# VS_Project_HW02.net
KiCad netlist of a schematic drawn in EasyEDA Pro
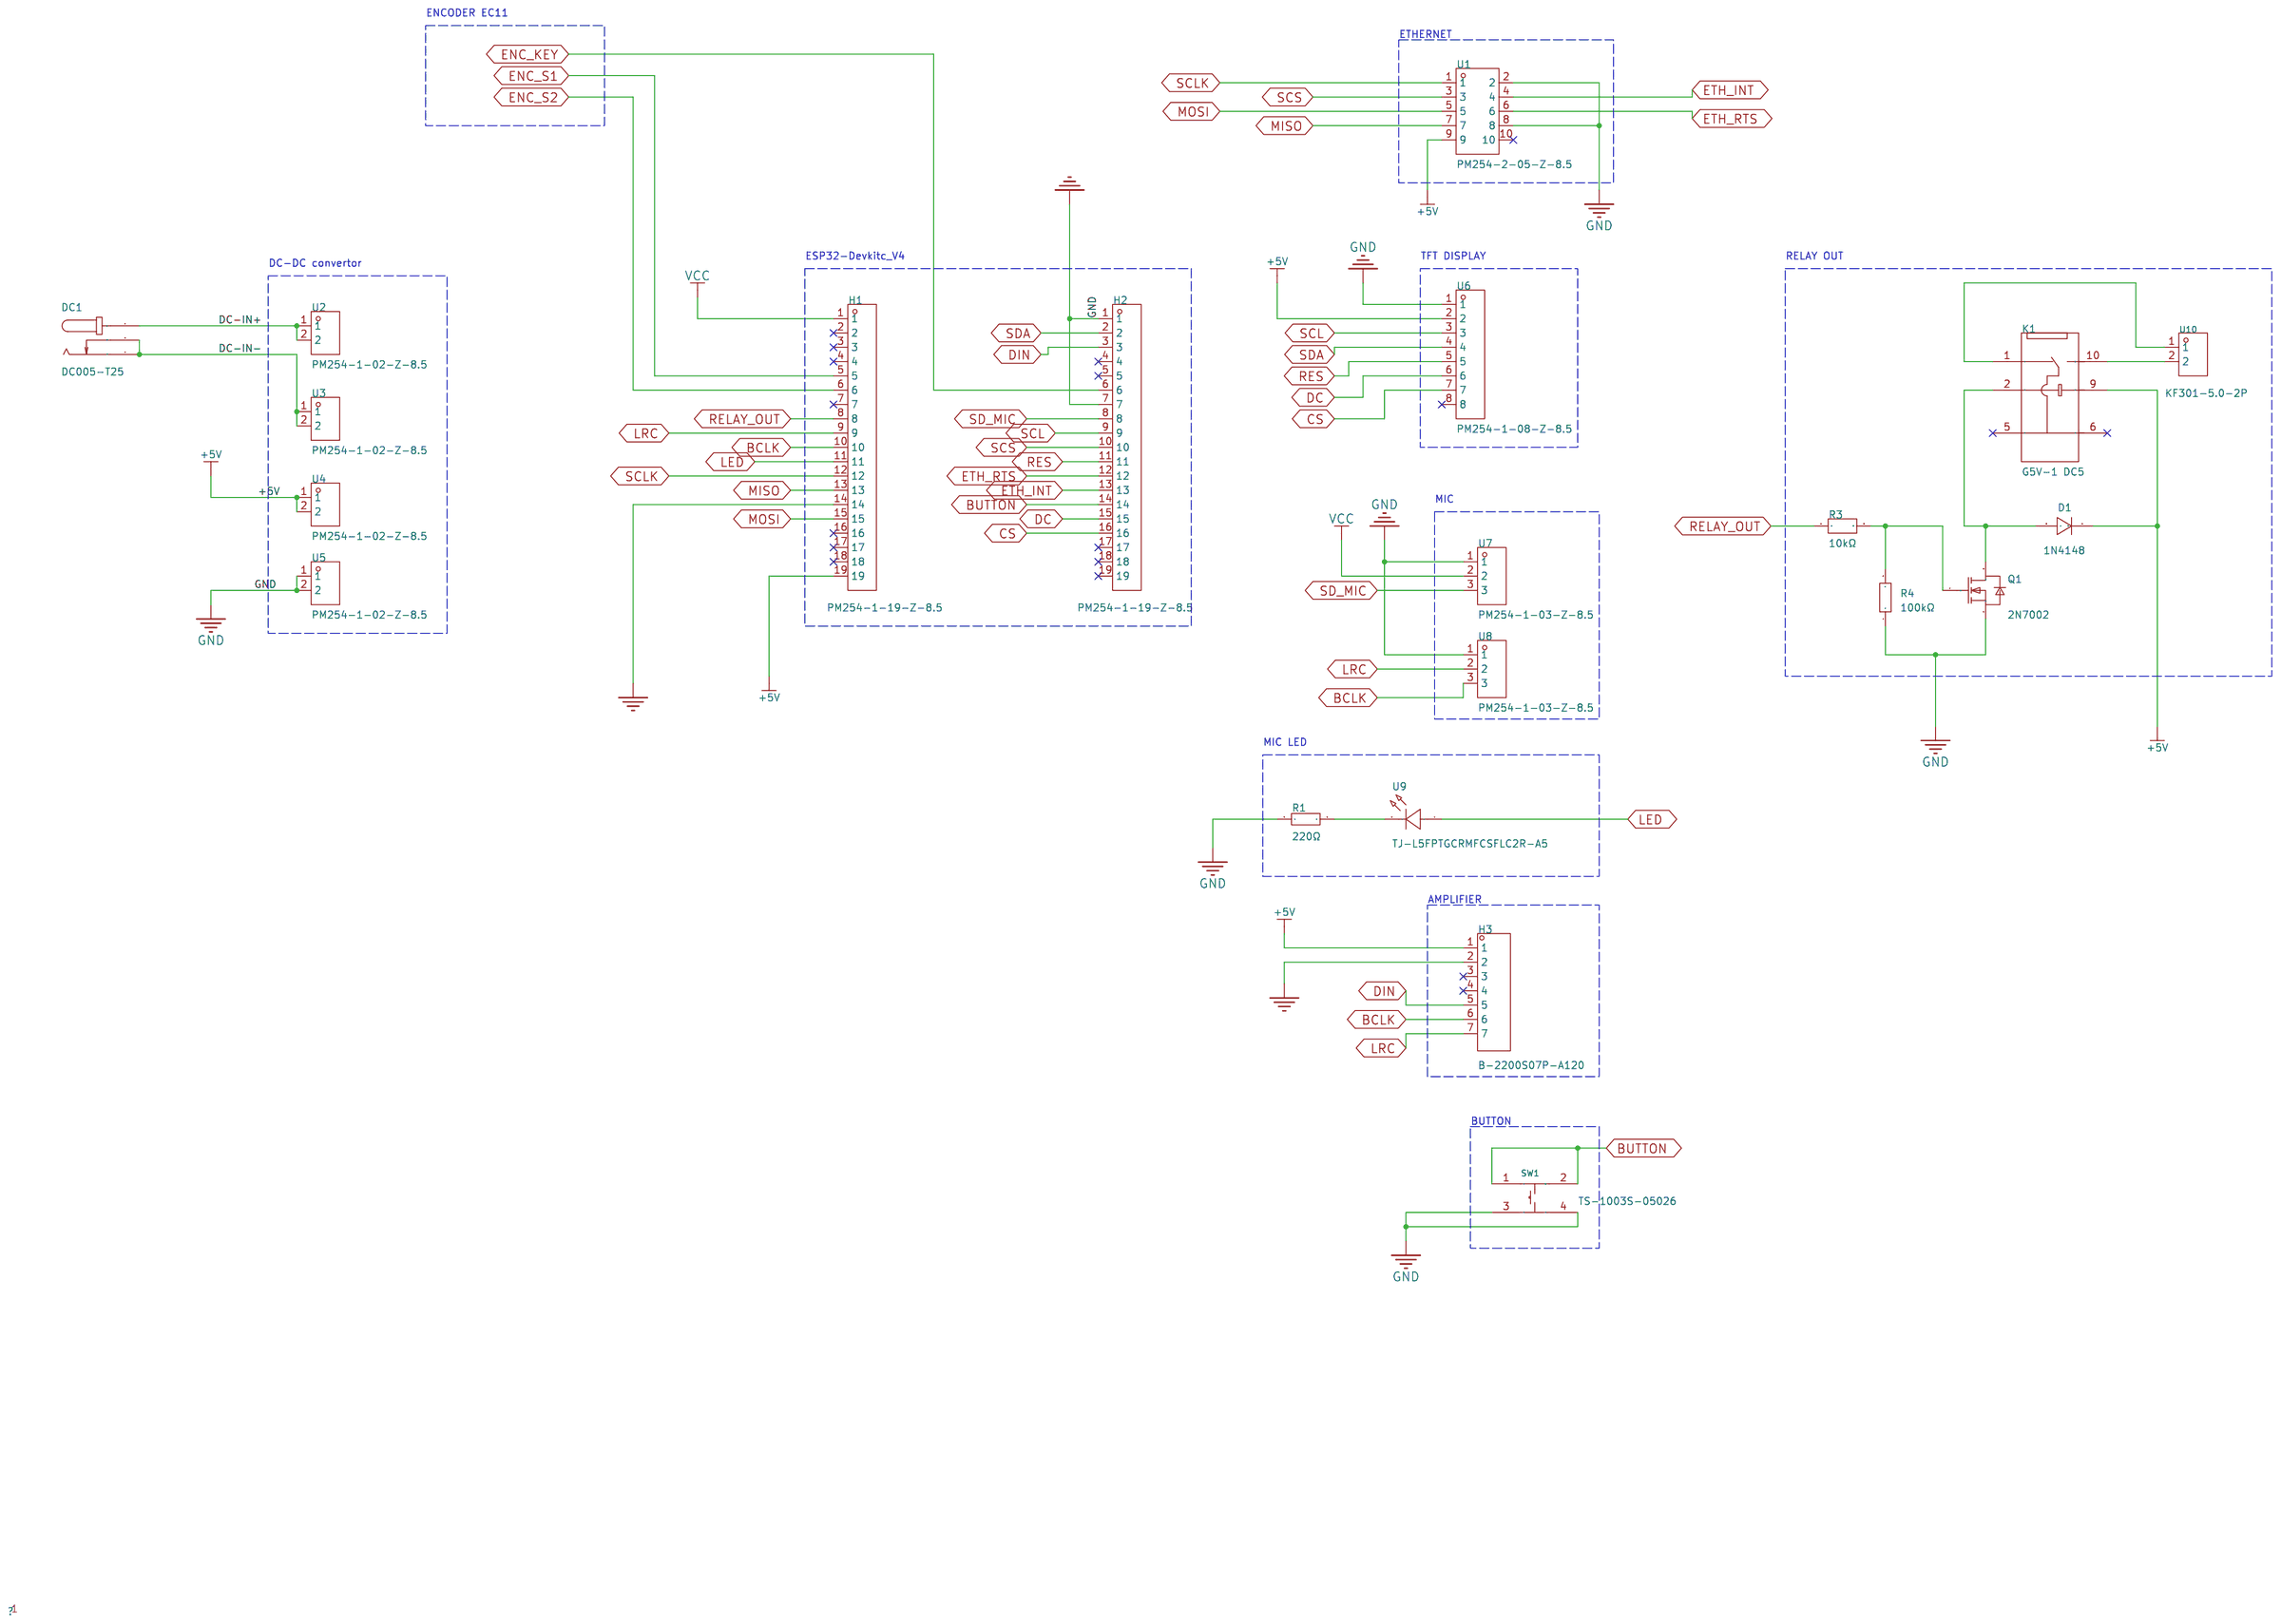
[diagram p0: schematic sheet]

(export (version "E")
  (design (tool "Eeschema 10.0.6"))
  (components
    (comp (ref "D1")
      (value "1N4148")
      (footprint "easyedapro:DO-35_BD2.0-L4.2-P8.20-D0.5-RD")
      (fields (field (name "Manufacturer") "GOOD-ARK(固锝)"))
      (libsource (lib "easyedapro") (part "1N4148_C406389"))
    )
    (comp (ref "DC1")
      (value "DC005-T25")
      (footprint "easyedapro:DC-IN-TH_DC-005-20A-1")
      (fields (field (name "Manufacturer") "SOFNG(硕方)"))
      (libsource (lib "easyedapro") (part "DC005-2.5MM"))
    )
    (comp (ref "H1")
      (value "PM254-1-19-Z-8.5")
      (footprint "easyedapro:HDR-TH_19P-P2.54-V-F")
      (fields (field (name "Manufacturer") "HCTL(华灿天禄)"))
      (libsource (lib "easyedapro") (part "HDR-F_2.54_1x19P"))
    )
    (comp (ref "H2")
      (value "PM254-1-19-Z-8.5")
      (footprint "easyedapro:HDR-TH_19P-P2.54-V-F")
      (fields (field (name "Manufacturer") "HCTL(华灿天禄)"))
      (libsource (lib "easyedapro") (part "HDR-F_2.54_1x19P"))
    )
    (comp (ref "H3")
      (value "B-2200S07P-A120")
      (footprint "easyedapro:HDR-TH_7P-P2.54-V-F")
      (fields (field (name "Manufacturer") "Ckmtw(灿科盟)"))
      (libsource (lib "easyedapro") (part "220S-1*7P H=8.5MM Ytype Gold-plated"))
    )
    (comp (ref "K1")
      (value "G5V-1 DC5")
      (footprint "easyedapro:RELAY-TH_G5V-1")
      (fields (field (name "Manufacturer") "OMRON(欧姆龙)"))
      (libsource (lib "easyedapro") (part "G5V-1-DC3"))
    )
    (comp (ref "Q1")
      (value "2N7002")
      (footprint "easyedapro:SOT-23-3_L2.9-W1.3-P1.90-LS2.4-BR")
      (fields (field (name "Manufacturer") "YFW(佑风微)"))
      (libsource (lib "easyedapro") (part "2N7002_C42395051"))
    )
    (comp (ref "R1")
      (value "220Ω")
      (footprint "easyedapro:R0603")
      (fields (field (name "Manufacturer Part") "RC0603FR-07220RL") (field (name "Manufacturer") "YAGEO(国巨)"))
      (libsource (lib "easyedapro") (part "Res"))
    )
    (comp (ref "R3")
      (value "10kΩ")
      (footprint "easyedapro:R0603")
      (fields (field (name "Manufacturer Part") "RC0603JR-0710KL") (field (name "Manufacturer") "YAGEO(国巨)"))
      (libsource (lib "easyedapro") (part "SCR0603J10K"))
    )
    (comp (ref "R4")
      (value "100kΩ")
      (footprint "easyedapro:R0603")
      (fields (field (name "Manufacturer Part") "RC0603FR-07100KL") (field (name "Manufacturer") "YAGEO(国巨)"))
      (libsource (lib "easyedapro") (part "Res"))
    )
    (comp (ref "SW1")
      (value "TS-1003S-05026")
      (footprint "easyedapro:KEY-SMD_4P-L12.0-W12.0-P5.00-LS15.2")
      (fields (field (name "Manufacturer") "XUNPU(讯普)"))
      (libsource (lib "easyedapro") (part "TS-1003S-05026"))
    )
    (comp (ref "U1")
      (value "PM254-2-05-Z-8.5")
      (footprint "easyedapro:HDR-TH_10P-P2.54-V-F-R2-C5-S2.54")
      (fields (field (name "Manufacturer") "HCTL(华灿天禄)"))
      (libsource (lib "easyedapro") (part "PM254-2-05-Z-8.5"))
    )
    (comp (ref "U2")
      (value "PM254-1-02-Z-8.5")
      (footprint "easyedapro:HDR-TH_2P-P2.54-V-F-3")
      (fields (field (name "Manufacturer") "HCTL(华灿天禄)"))
      (libsource (lib "easyedapro") (part "PM254-1-02-Z-8.5_C3012024"))
    )
    (comp (ref "U3")
      (value "PM254-1-02-Z-8.5")
      (footprint "easyedapro:HDR-TH_2P-P2.54-V-F-3")
      (fields (field (name "Manufacturer") "HCTL(华灿天禄)"))
      (libsource (lib "easyedapro") (part "PM254-1-02-Z-8.5_C3012024"))
    )
    (comp (ref "U4")
      (value "PM254-1-02-Z-8.5")
      (footprint "easyedapro:HDR-TH_2P-P2.54-V-F-3")
      (fields (field (name "Manufacturer") "HCTL(华灿天禄)"))
      (libsource (lib "easyedapro") (part "PM254-1-02-Z-8.5_C3012024"))
    )
    (comp (ref "U5")
      (value "PM254-1-02-Z-8.5")
      (footprint "easyedapro:HDR-TH_2P-P2.54-V-F-3")
      (fields (field (name "Manufacturer") "HCTL(华灿天禄)"))
      (libsource (lib "easyedapro") (part "PM254-1-02-Z-8.5_C3012024"))
    )
    (comp (ref "U6")
      (value "PM254-1-08-Z-8.5")
      (footprint "easyedapro:HDR-TH_8P-P2.54-V-F")
      (fields (field (name "Manufacturer") "HCTL(华灿天禄)"))
      (libsource (lib "easyedapro") (part "PM254-1-08-Z-8.5"))
    )
    (comp (ref "U7")
      (value "PM254-1-03-Z-8.5")
      (footprint "easyedapro:HDR-TH_3P-P2.54-V-F")
      (fields (field (name "Manufacturer") "HCTL(华灿天禄)"))
      (libsource (lib "easyedapro") (part "PM254-1-03-Z-8.5"))
    )
    (comp (ref "U8")
      (value "PM254-1-03-Z-8.5")
      (footprint "easyedapro:HDR-TH_3P-P2.54-V-F")
      (fields (field (name "Manufacturer") "HCTL(华灿天禄)"))
      (libsource (lib "easyedapro") (part "PM254-1-03-Z-8.5"))
    )
    (comp (ref "U9")
      (value "TJ-L5FPTGCRMFCSFLC2R-A5")
      (footprint "easyedapro:LED-TH_BD5.8-P2.54-FD")
      (description "Lamp Holder Type:5mm圆柱形灯头 Emitted Color:Red Lens Color:雾状红透镜")
      (fields (field (name "Manufacturer") "TOGIALED(统佳)"))
      (libsource (lib "easyedapro") (part "TJ-L5FPTGCRMFCSFLC2R-A5"))
    )
    (comp (ref "U10")
      (value "KF301-5.0-2P")
      (footprint "easyedapro:CONN-TH_P5.00_KF301-5.0-2P")
      (fields (field (name "Manufacturer") "KEFA(科发)"))
      (libsource (lib "easyedapro") (part "KF301-5.0-2P"))
    )
  )
  (nets
    (net (code "1") (name "+5V") (class "Default")
      (node (ref "D1") (pin "1") (pinfunction "C_1") (pintype "unspecified"))
      (node (ref "H1") (pin "19") (pinfunction "19_19") (pintype "input"))
      (node (ref "H3") (pin "1") (pinfunction "1_1") (pintype "unspecified"))
      (node (ref "K1") (pin "9") (pinfunction "9_9") (pintype "input"))
      (node (ref "U1") (pin "9") (pinfunction "9_9") (pintype "unspecified"))
      (node (ref "U4") (pin "1") (pinfunction "1_1") (pintype "unspecified"))
      (node (ref "U4") (pin "2") (pinfunction "2_2") (pintype "unspecified"))
      (node (ref "U6") (pin "2") (pinfunction "2_2") (pintype "unspecified"))
    )
    (net (code "2") (name "/DC-IN+") (class "Default")
      (node (ref "DC1") (pin "1") (pinfunction "1_1") (pintype "unspecified"))
      (node (ref "U2") (pin "1") (pinfunction "1_1") (pintype "unspecified"))
      (node (ref "U2") (pin "2") (pinfunction "2_2") (pintype "unspecified"))
    )
    (net (code "3") (name "/DC-IN-") (class "Default")
      (node (ref "DC1") (pin "2") (pinfunction "2_2") (pintype "unspecified"))
      (node (ref "DC1") (pin "3") (pinfunction "3_3") (pintype "unspecified"))
      (node (ref "U3") (pin "1") (pinfunction "1_1") (pintype "unspecified"))
      (node (ref "U3") (pin "2") (pinfunction "2_2") (pintype "unspecified"))
    )
    (net (code "4") (name "BCLK") (class "Default")
      (node (ref "H1") (pin "10") (pinfunction "10_10") (pintype "input"))
      (node (ref "H3") (pin "6") (pinfunction "6_6") (pintype "unspecified"))
      (node (ref "U8") (pin "3") (pinfunction "3_3") (pintype "unspecified"))
    )
    (net (code "5") (name "BUTTON") (class "Default")
      (node (ref "H2") (pin "14") (pinfunction "14_14") (pintype "input"))
      (node (ref "SW1") (pin "1") (pinfunction "1_1") (pintype "input"))
      (node (ref "SW1") (pin "2") (pinfunction "2_2") (pintype "input"))
    )
    (net (code "6") (name "CS") (class "Default")
      (node (ref "H2") (pin "16") (pinfunction "16_16") (pintype "input"))
      (node (ref "U6") (pin "7") (pinfunction "7_7") (pintype "unspecified"))
    )
    (net (code "7") (name "DC") (class "Default")
      (node (ref "H2") (pin "15") (pinfunction "15_15") (pintype "input"))
      (node (ref "U6") (pin "6") (pinfunction "6_6") (pintype "unspecified"))
    )
    (net (code "8") (name "DIN") (class "Default")
      (node (ref "H2") (pin "3") (pinfunction "3_3") (pintype "input"))
      (node (ref "H3") (pin "5") (pinfunction "5_5") (pintype "unspecified"))
    )
    (net (code "9") (name "ENC_KEY") (class "Default")
      (node (ref "H2") (pin "6") (pinfunction "6_6") (pintype "input"))
    )
    (net (code "10") (name "ENC_S1") (class "Default")
      (node (ref "H1") (pin "5") (pinfunction "5_5") (pintype "input"))
    )
    (net (code "11") (name "ENC_S2") (class "Default")
      (node (ref "H1") (pin "6") (pinfunction "6_6") (pintype "input"))
    )
    (net (code "12") (name "ETH_INT") (class "Default")
      (node (ref "H2") (pin "13") (pinfunction "13_13") (pintype "input"))
      (node (ref "U1") (pin "4") (pinfunction "4_4") (pintype "unspecified"))
    )
    (net (code "13") (name "ETH_RTS") (class "Default")
      (node (ref "H2") (pin "12") (pinfunction "12_12") (pintype "input"))
      (node (ref "U1") (pin "6") (pinfunction "6_6") (pintype "unspecified"))
    )
    (net (code "14") (name "GND") (class "Default")
      (node (ref "H1") (pin "14") (pinfunction "14_14") (pintype "input"))
      (node (ref "H2") (pin "1") (pinfunction "1_1") (pintype "input"))
      (node (ref "H2") (pin "7") (pinfunction "7_7") (pintype "input"))
      (node (ref "H3") (pin "2") (pinfunction "2_2") (pintype "unspecified"))
      (node (ref "Q1") (pin "2") (pinfunction "S_2") (pintype "unspecified"))
      (node (ref "R1") (pin "1") (pinfunction "1_1") (pintype "input"))
      (node (ref "R4") (pin "1") (pinfunction "1_1") (pintype "input"))
      (node (ref "SW1") (pin "3") (pinfunction "3_3") (pintype "input"))
      (node (ref "SW1") (pin "4") (pinfunction "4_4") (pintype "input"))
      (node (ref "U1") (pin "2") (pinfunction "2_2") (pintype "unspecified"))
      (node (ref "U1") (pin "8") (pinfunction "8_8") (pintype "unspecified"))
      (node (ref "U5") (pin "1") (pinfunction "1_1") (pintype "unspecified"))
      (node (ref "U5") (pin "2") (pinfunction "2_2") (pintype "unspecified"))
      (node (ref "U6") (pin "1") (pinfunction "1_1") (pintype "unspecified"))
      (node (ref "U7") (pin "1") (pinfunction "1_1") (pintype "unspecified"))
      (node (ref "U8") (pin "1") (pinfunction "1_1") (pintype "unspecified"))
    )
    (net (code "15") (name "LED") (class "Default")
      (node (ref "H1") (pin "11") (pinfunction "11_11") (pintype "input"))
      (node (ref "U9") (pin "1") (pinfunction "A_1") (pintype "unspecified"))
    )
    (net (code "16") (name "LRC") (class "Default")
      (node (ref "H1") (pin "9") (pinfunction "9_9") (pintype "input"))
      (node (ref "H3") (pin "7") (pinfunction "7_7") (pintype "unspecified"))
      (node (ref "U8") (pin "2") (pinfunction "2_2") (pintype "unspecified"))
    )
    (net (code "17") (name "MISO") (class "Default")
      (node (ref "H1") (pin "13") (pinfunction "13_13") (pintype "input"))
      (node (ref "U1") (pin "7") (pinfunction "7_7") (pintype "unspecified"))
    )
    (net (code "18") (name "MOSI") (class "Default")
      (node (ref "H1") (pin "15") (pinfunction "15_15") (pintype "input"))
      (node (ref "U1") (pin "5") (pinfunction "5_5") (pintype "unspecified"))
    )
    (net (code "19") (name "Net-(D1-A)") (class "Default")
      (node (ref "D1") (pin "2") (pinfunction "A_2") (pintype "unspecified"))
      (node (ref "K1") (pin "2") (pinfunction "2_2") (pintype "input"))
      (node (ref "Q1") (pin "3") (pinfunction "D_3") (pintype "unspecified"))
    )
    (net (code "20") (name "Net-(K1-Pad1)") (class "Default")
      (node (ref "K1") (pin "1") (pinfunction "1_1") (pintype "input"))
      (node (ref "U10") (pin "1") (pinfunction "1_1") (pintype "input"))
    )
    (net (code "21") (name "Net-(K1-Pad10)") (class "Default")
      (node (ref "K1") (pin "10") (pinfunction "10_10") (pintype "input"))
      (node (ref "U10") (pin "2") (pinfunction "2_2") (pintype "input"))
    )
    (net (code "22") (name "Net-(Q1-G)") (class "Default")
      (node (ref "Q1") (pin "1") (pinfunction "G_1") (pintype "unspecified"))
      (node (ref "R3") (pin "2") (pinfunction "2_2") (pintype "unspecified"))
      (node (ref "R4") (pin "2") (pinfunction "2_2") (pintype "input"))
    )
    (net (code "23") (name "Net-(U9-K)") (class "Default")
      (node (ref "R1") (pin "2") (pinfunction "2_2") (pintype "input"))
      (node (ref "U9") (pin "2") (pinfunction "K_2") (pintype "unspecified"))
    )
    (net (code "24") (name "RELAY_OUT") (class "Default")
      (node (ref "H1") (pin "8") (pinfunction "8_8") (pintype "input"))
      (node (ref "R3") (pin "1") (pinfunction "1_1") (pintype "unspecified"))
    )
    (net (code "25") (name "RES") (class "Default")
      (node (ref "H2") (pin "11") (pinfunction "11_11") (pintype "input"))
      (node (ref "U6") (pin "5") (pinfunction "5_5") (pintype "unspecified"))
    )
    (net (code "26") (name "SCL") (class "Default")
      (node (ref "H2") (pin "9") (pinfunction "9_9") (pintype "input"))
      (node (ref "U6") (pin "3") (pinfunction "3_3") (pintype "unspecified"))
    )
    (net (code "27") (name "SCLK") (class "Default")
      (node (ref "H1") (pin "12") (pinfunction "12_12") (pintype "input"))
      (node (ref "U1") (pin "1") (pinfunction "1_1") (pintype "unspecified"))
    )
    (net (code "28") (name "SCS") (class "Default")
      (node (ref "H2") (pin "10") (pinfunction "10_10") (pintype "input"))
      (node (ref "U1") (pin "3") (pinfunction "3_3") (pintype "unspecified"))
    )
    (net (code "29") (name "SDA") (class "Default")
      (node (ref "H2") (pin "2") (pinfunction "2_2") (pintype "input"))
      (node (ref "U6") (pin "4") (pinfunction "4_4") (pintype "unspecified"))
    )
    (net (code "30") (name "SD_MIC") (class "Default")
      (node (ref "H2") (pin "8") (pinfunction "8_8") (pintype "input"))
      (node (ref "U7") (pin "3") (pinfunction "3_3") (pintype "unspecified"))
    )
    (net (code "31") (name "VCC") (class "Default")
      (node (ref "H1") (pin "1") (pinfunction "1_1") (pintype "input"))
      (node (ref "U7") (pin "2") (pinfunction "2_2") (pintype "unspecified"))
    )
    (net (code "32") (name "unconnected-(H1-Pad2)") (class "Default")
      (node (ref "H1") (pin "2") (pinfunction "2_2") (pintype "input+no_connect"))
    )
    (net (code "33") (name "unconnected-(H1-Pad3)") (class "Default")
      (node (ref "H1") (pin "3") (pinfunction "3_3") (pintype "input+no_connect"))
    )
    (net (code "34") (name "unconnected-(H1-Pad4)") (class "Default")
      (node (ref "H1") (pin "4") (pinfunction "4_4") (pintype "input+no_connect"))
    )
    (net (code "35") (name "unconnected-(H1-Pad7)") (class "Default")
      (node (ref "H1") (pin "7") (pinfunction "7_7") (pintype "input+no_connect"))
    )
    (net (code "36") (name "unconnected-(H1-Pad16)") (class "Default")
      (node (ref "H1") (pin "16") (pinfunction "16_16") (pintype "input+no_connect"))
    )
    (net (code "37") (name "unconnected-(H1-Pad17)") (class "Default")
      (node (ref "H1") (pin "17") (pinfunction "17_17") (pintype "input+no_connect"))
    )
    (net (code "38") (name "unconnected-(H1-Pad18)") (class "Default")
      (node (ref "H1") (pin "18") (pinfunction "18_18") (pintype "input+no_connect"))
    )
    (net (code "39") (name "unconnected-(H2-Pad4)") (class "Default")
      (node (ref "H2") (pin "4") (pinfunction "4_4") (pintype "input+no_connect"))
    )
    (net (code "40") (name "unconnected-(H2-Pad5)") (class "Default")
      (node (ref "H2") (pin "5") (pinfunction "5_5") (pintype "input+no_connect"))
    )
    (net (code "41") (name "unconnected-(H2-Pad17)") (class "Default")
      (node (ref "H2") (pin "17") (pinfunction "17_17") (pintype "input+no_connect"))
    )
    (net (code "42") (name "unconnected-(H2-Pad18)") (class "Default")
      (node (ref "H2") (pin "18") (pinfunction "18_18") (pintype "input+no_connect"))
    )
    (net (code "43") (name "unconnected-(H2-Pad19)") (class "Default")
      (node (ref "H2") (pin "19") (pinfunction "19_19") (pintype "input+no_connect"))
    )
    (net (code "44") (name "unconnected-(H3-Pad3)") (class "Default")
      (node (ref "H3") (pin "3") (pinfunction "3_3") (pintype "unspecified+no_connect"))
    )
    (net (code "45") (name "unconnected-(H3-Pad4)") (class "Default")
      (node (ref "H3") (pin "4") (pinfunction "4_4") (pintype "unspecified+no_connect"))
    )
    (net (code "46") (name "unconnected-(K1-Pad5)") (class "Default")
      (node (ref "K1") (pin "5") (pinfunction "5_5") (pintype "input+no_connect"))
    )
    (net (code "47") (name "unconnected-(K1-Pad6)") (class "Default")
      (node (ref "K1") (pin "6") (pinfunction "6_6") (pintype "input+no_connect"))
    )
    (net (code "48") (name "unconnected-(U1-Pad10)") (class "Default")
      (node (ref "U1") (pin "10") (pinfunction "10_10") (pintype "unspecified+no_connect"))
    )
    (net (code "49") (name "unconnected-(U6-Pad8)") (class "Default")
      (node (ref "U6") (pin "8") (pinfunction "8_8") (pintype "unspecified+no_connect"))
    )
  )
)
